# VCF-LM324-Stereo-Perfboard.net
KiCad netlist of a schematic drawn in EAGLE
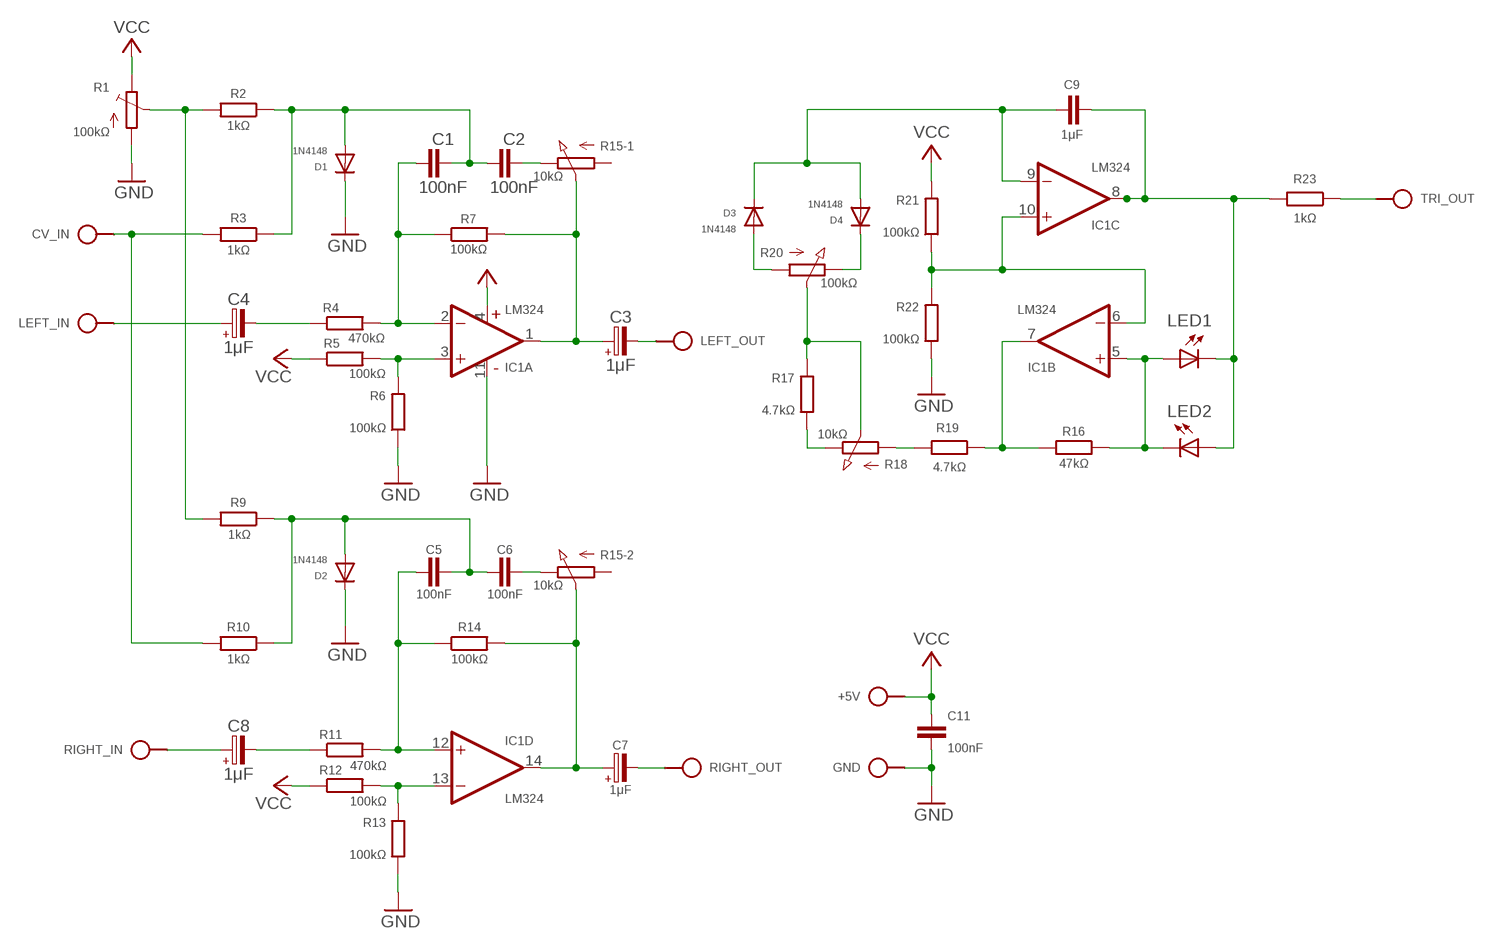
[diagram p0: schematic, sheet 1]

(export (version "E")
  (design (tool "Eeschema 10.0.6"))
  (components
    (comp (ref "+5V")
      (value "VCC")
      (footprint "eagle-import:SPAD")
      (libsource (lib "eagle-import") (part "SPAD"))
    )
    (comp (ref "C1")
      (value "100nF")
      (footprint "eagle-import:C050-024X044")
      (libsource (lib "eagle-import") (part "C050-024X044"))
    )
    (comp (ref "C2")
      (value "100nF")
      (footprint "eagle-import:C050-024X044")
      (libsource (lib "eagle-import") (part "C050-024X044"))
    )
    (comp (ref "C3")
      (value "1μF")
      (footprint "eagle-import:E2,5-3")
      (libsource (lib "eagle-import") (part "CPOLE2,5-3"))
    )
    (comp (ref "C4")
      (value "1μF")
      (footprint "eagle-import:E2,5-3")
      (libsource (lib "eagle-import") (part "CPOLE2,5-3"))
    )
    (comp (ref "C5")
      (value "100nF")
      (footprint "eagle-import:C050-024X044")
      (libsource (lib "eagle-import") (part "C050-024X044"))
    )
    (comp (ref "C6")
      (value "100nF")
      (footprint "eagle-import:C050-024X044")
      (libsource (lib "eagle-import") (part "C050-024X044"))
    )
    (comp (ref "C7")
      (value "1μF")
      (footprint "eagle-import:E2,5-3")
      (libsource (lib "eagle-import") (part "CPOLE2,5-3"))
    )
    (comp (ref "C8")
      (value "1μF")
      (footprint "eagle-import:E2,5-3")
      (libsource (lib "eagle-import") (part "CPOLE2,5-3"))
    )
    (comp (ref "C9")
      (value "1μF")
      (footprint "eagle-import:C050-024X044")
      (libsource (lib "eagle-import") (part "C050-024X044"))
    )
    (comp (ref "C11")
      (value "100nF")
      (footprint "eagle-import:C050-020X036")
      (libsource (lib "eagle-import") (part "C050-020X036"))
    )
    (comp (ref "CV_IN")
      (value "CV_IN")
      (footprint "eagle-import:SPAD")
      (libsource (lib "eagle-import") (part "SPAD"))
    )
    (comp (ref "D1")
      (value "1N4148")
      (footprint "eagle-import:DO34-10V")
      (libsource (lib "eagle-import") (part "1N414834-10V"))
    )
    (comp (ref "D2")
      (value "1N4148")
      (footprint "eagle-import:DO34-7V")
      (libsource (lib "eagle-import") (part "1N414834-7V"))
    )
    (comp (ref "D3")
      (value "1N4148")
      (footprint "eagle-import:DO34-7V")
      (libsource (lib "eagle-import") (part "1N414834-7V"))
    )
    (comp (ref "D4")
      (value "1N4148")
      (footprint "eagle-import:DO34-7V")
      (libsource (lib "eagle-import") (part "1N414834-7V"))
    )
    (comp (ref "GND")
      (value "GND")
      (footprint "eagle-import:SPAD")
      (libsource (lib "eagle-import") (part "SPAD"))
    )
    (comp (ref "IC1")
      (value "LM324")
      (footprint "eagle-import:DIL14")
      (libsource (lib "eagle-import") (part "LM324N"))
    )
    (comp (ref "LED1")
      (value "LED3MM")
      (footprint "eagle-import:LED3MM")
      (libsource (lib "eagle-import") (part "LED3MM"))
    )
    (comp (ref "LED2")
      (value "LED3MM")
      (footprint "eagle-import:LED3MM")
      (libsource (lib "eagle-import") (part "LED3MM"))
    )
    (comp (ref "LEFT_IN")
      (value "AUDIO_IN")
      (footprint "eagle-import:SPAD")
      (libsource (lib "eagle-import") (part "SPAD"))
    )
    (comp (ref "LEFT_OUT")
      (value "AUDIO_OUT")
      (footprint "eagle-import:SPAD")
      (libsource (lib "eagle-import") (part "SPAD"))
    )
    (comp (ref "R1")
      (value "100kΩ")
      (footprint "eagle-import:B64Y")
      (libsource (lib "eagle-import") (part "TRIM"))
    )
    (comp (ref "R2")
      (value "1kΩ")
      (footprint "eagle-import:0202_7")
      (libsource (lib "eagle-import") (part "R0202/7"))
    )
    (comp (ref "R3")
      (value "1kΩ")
      (footprint "eagle-import:0202_7")
      (libsource (lib "eagle-import") (part "R0202/7"))
    )
    (comp (ref "R4")
      (value "470kΩ")
      (footprint "eagle-import:0202_7")
      (libsource (lib "eagle-import") (part "R0202/7"))
    )
    (comp (ref "R5")
      (value "100kΩ")
      (footprint "eagle-import:0204_7")
      (libsource (lib "eagle-import") (part "R0204/7"))
    )
    (comp (ref "R6")
      (value "100kΩ")
      (footprint "eagle-import:0202_7")
      (libsource (lib "eagle-import") (part "R0202/7"))
    )
    (comp (ref "R7")
      (value "100kΩ")
      (footprint "eagle-import:0204_7")
      (libsource (lib "eagle-import") (part "R0204/7"))
    )
    (comp (ref "R9")
      (value "1kΩ")
      (footprint "eagle-import:0202_10")
      (libsource (lib "eagle-import") (part "R0202/10"))
    )
    (comp (ref "R10")
      (value "1kΩ")
      (footprint "eagle-import:0202_10")
      (libsource (lib "eagle-import") (part "R0202/10"))
    )
    (comp (ref "R11")
      (value "470kΩ")
      (footprint "eagle-import:0202_7")
      (libsource (lib "eagle-import") (part "R0202/7"))
    )
    (comp (ref "R12")
      (value "100kΩ")
      (footprint "eagle-import:0202_7")
      (libsource (lib "eagle-import") (part "R0202/7"))
    )
    (comp (ref "R13")
      (value "100kΩ")
      (footprint "eagle-import:0202_7")
      (libsource (lib "eagle-import") (part "R0202/7"))
    )
    (comp (ref "R14")
      (value "100kΩ")
      (footprint "eagle-import:0204_10")
      (libsource (lib "eagle-import") (part "R0204/10"))
    )
    (comp (ref "R15")
      (value "10kΩ")
      (footprint "eagle-import:POT-STEREO-2X3")
      (libsource (lib "eagle-import") (part "POT-STEREO"))
    )
    (comp (ref "R16")
      (value "47kΩ")
      (footprint "eagle-import:0202_7-V")
      (libsource (lib "eagle-import") (part "R0202/7-V"))
    )
    (comp (ref "R17")
      (value "4.7kΩ")
      (footprint "eagle-import:0202_7")
      (libsource (lib "eagle-import") (part "R0202/7"))
    )
    (comp (ref "R18")
      (value "10kΩ")
      (footprint "eagle-import:POT")
      (libsource (lib "eagle-import") (part "POT"))
    )
    (comp (ref "R19")
      (value "4.7kΩ")
      (footprint "eagle-import:0202_7-V")
      (libsource (lib "eagle-import") (part "R0202/7-V"))
    )
    (comp (ref "R20")
      (value "100kΩ")
      (footprint "eagle-import:POT")
      (libsource (lib "eagle-import") (part "POT"))
    )
    (comp (ref "R21")
      (value "100kΩ")
      (footprint "eagle-import:0202_7-V")
      (libsource (lib "eagle-import") (part "R0202/7-V"))
    )
    (comp (ref "R22")
      (value "100kΩ")
      (footprint "eagle-import:0202_7-V")
      (libsource (lib "eagle-import") (part "R0202/7-V"))
    )
    (comp (ref "R23")
      (value "1kΩ")
      (footprint "eagle-import:0202_7-V")
      (libsource (lib "eagle-import") (part "R0202/7-V"))
    )
    (comp (ref "RIGHT_IN")
      (value "AUDIO_IN")
      (footprint "eagle-import:SPAD")
      (libsource (lib "eagle-import") (part "SPAD"))
    )
    (comp (ref "RIGHT_OUT")
      (value "AUDIO_OUT")
      (footprint "eagle-import:SPAD")
      (libsource (lib "eagle-import") (part "SPAD"))
    )
    (comp (ref "TRI_OUT")
      (value "TRIANGLE")
      (footprint "eagle-import:SPAD")
      (libsource (lib "eagle-import") (part "SPAD"))
    )
  )
  (nets
    (net (code "1") (name "GND") (class "Default")
      (node (ref "C11") (pin "2") (pinfunction "2_2") (pintype "passive"))
      (node (ref "D1") (pin "C") (pinfunction "C_C") (pintype "passive"))
      (node (ref "D2") (pin "C") (pinfunction "C_C") (pintype "passive"))
      (node (ref "GND") (pin "1") (pinfunction "P$1_1") (pintype "bidirectional"))
      (node (ref "IC1") (pin "11") (pinfunction "V-_11") (pintype "power_in"))
      (node (ref "R1") (pin "A") (pinfunction "A_A") (pintype "passive"))
      (node (ref "R13") (pin "1") (pinfunction "1_1") (pintype "passive"))
      (node (ref "R22") (pin "1") (pinfunction "1_1") (pintype "passive"))
      (node (ref "R6") (pin "1") (pinfunction "1_1") (pintype "passive"))
    )
    (net (code "2") (name "Net-(C1-Pad2)") (class "Default")
      (node (ref "C1") (pin "2") (pinfunction "2_2") (pintype "passive"))
      (node (ref "C2") (pin "1") (pinfunction "1_1") (pintype "passive"))
      (node (ref "D1") (pin "A") (pinfunction "A_A") (pintype "passive"))
      (node (ref "R2") (pin "1") (pinfunction "1_1") (pintype "passive"))
      (node (ref "R3") (pin "1") (pinfunction "1_1") (pintype "passive"))
    )
    (net (code "3") (name "Net-(C4-Pad-)") (class "Default")
      (node (ref "C4") (pin "-") (pinfunction "-_-") (pintype "passive"))
      (node (ref "R4") (pin "1") (pinfunction "1_1") (pintype "passive"))
    )
    (net (code "4") (name "Net-(C5-Pad2)") (class "Default")
      (node (ref "C5") (pin "2") (pinfunction "2_2") (pintype "passive"))
      (node (ref "C6") (pin "1") (pinfunction "1_1") (pintype "passive"))
      (node (ref "D2") (pin "A") (pinfunction "A_A") (pintype "passive"))
      (node (ref "R10") (pin "1") (pinfunction "1_1") (pintype "passive"))
      (node (ref "R9") (pin "1") (pinfunction "1_1") (pintype "passive"))
    )
    (net (code "5") (name "Net-(C8-Pad-)") (class "Default")
      (node (ref "C8") (pin "-") (pinfunction "-_-") (pintype "passive"))
      (node (ref "R11") (pin "1") (pinfunction "1_1") (pintype "passive"))
    )
    (net (code "6") (name "Net-(CV_IN-P$1)") (class "Default")
      (node (ref "CV_IN") (pin "1") (pinfunction "P$1_1") (pintype "bidirectional"))
      (node (ref "R10") (pin "2") (pinfunction "2_2") (pintype "passive"))
      (node (ref "R3") (pin "2") (pinfunction "2_2") (pintype "passive"))
    )
    (net (code "7") (name "Net-(IC1A-+IN)") (class "Default")
      (node (ref "IC1") (pin "3") (pinfunction "+IN_3") (pintype "input"))
      (node (ref "R5") (pin "2") (pinfunction "2_2") (pintype "passive"))
      (node (ref "R6") (pin "2") (pinfunction "2_2") (pintype "passive"))
    )
    (net (code "8") (name "Net-(IC1A--IN)") (class "Default")
      (node (ref "C1") (pin "1") (pinfunction "1_1") (pintype "passive"))
      (node (ref "IC1") (pin "2") (pinfunction "-IN_2") (pintype "input"))
      (node (ref "R4") (pin "2") (pinfunction "2_2") (pintype "passive"))
      (node (ref "R7") (pin "1") (pinfunction "1_1") (pintype "passive"))
    )
    (net (code "9") (name "Net-(IC1A-OUT)") (class "Default")
      (node (ref "C3") (pin "+") (pinfunction "+_+") (pintype "passive"))
      (node (ref "IC1") (pin "1") (pinfunction "OUT_1") (pintype "output"))
      (node (ref "R15") (pin "1-S") (pinfunction "S_1-S") (pintype "passive"))
      (node (ref "R7") (pin "2") (pinfunction "2_2") (pintype "passive"))
    )
    (net (code "10") (name "Net-(IC1B-+IN)") (class "Default")
      (node (ref "IC1") (pin "5") (pinfunction "+IN_5") (pintype "input"))
      (node (ref "LED1") (pin "A") (pinfunction "A_A") (pintype "passive"))
      (node (ref "LED2") (pin "K") (pinfunction "C_K") (pintype "passive"))
      (node (ref "R16") (pin "1") (pinfunction "1_1") (pintype "passive"))
    )
    (net (code "11") (name "Net-(IC1B--IN)") (class "Default")
      (node (ref "IC1") (pin "10") (pinfunction "+IN_10") (pintype "input"))
      (node (ref "IC1") (pin "6") (pinfunction "-IN_6") (pintype "input"))
      (node (ref "R21") (pin "1") (pinfunction "1_1") (pintype "passive"))
      (node (ref "R22") (pin "2") (pinfunction "2_2") (pintype "passive"))
    )
    (net (code "12") (name "Net-(IC1B-OUT)") (class "Default")
      (node (ref "IC1") (pin "7") (pinfunction "OUT_7") (pintype "output"))
      (node (ref "R16") (pin "2") (pinfunction "2_2") (pintype "passive"))
      (node (ref "R19") (pin "1") (pinfunction "1_1") (pintype "passive"))
    )
    (net (code "13") (name "Net-(IC1C--IN)") (class "Default")
      (node (ref "C9") (pin "1") (pinfunction "1_1") (pintype "passive"))
      (node (ref "D3") (pin "C") (pinfunction "C_C") (pintype "passive"))
      (node (ref "D4") (pin "A") (pinfunction "A_A") (pintype "passive"))
      (node (ref "IC1") (pin "9") (pinfunction "-IN_9") (pintype "input"))
    )
    (net (code "14") (name "Net-(IC1C-OUT)") (class "Default")
      (node (ref "C9") (pin "2") (pinfunction "2_2") (pintype "passive"))
      (node (ref "IC1") (pin "8") (pinfunction "OUT_8") (pintype "output"))
      (node (ref "LED1") (pin "K") (pinfunction "C_K") (pintype "passive"))
      (node (ref "LED2") (pin "A") (pinfunction "A_A") (pintype "passive"))
      (node (ref "R23") (pin "2") (pinfunction "2_2") (pintype "passive"))
    )
    (net (code "15") (name "Net-(IC1D-+IN)") (class "Default")
      (node (ref "C5") (pin "1") (pinfunction "1_1") (pintype "passive"))
      (node (ref "IC1") (pin "12") (pinfunction "+IN_12") (pintype "input"))
      (node (ref "R11") (pin "2") (pinfunction "2_2") (pintype "passive"))
      (node (ref "R14") (pin "1") (pinfunction "1_1") (pintype "passive"))
    )
    (net (code "16") (name "Net-(IC1D--IN)") (class "Default")
      (node (ref "IC1") (pin "13") (pinfunction "-IN_13") (pintype "input"))
      (node (ref "R12") (pin "2") (pinfunction "2_2") (pintype "passive"))
      (node (ref "R13") (pin "2") (pinfunction "2_2") (pintype "passive"))
    )
    (net (code "17") (name "Net-(IC1D-OUT)") (class "Default")
      (node (ref "C7") (pin "+") (pinfunction "+_+") (pintype "passive"))
      (node (ref "IC1") (pin "14") (pinfunction "OUT_14") (pintype "output"))
      (node (ref "R14") (pin "2") (pinfunction "2_2") (pintype "passive"))
      (node (ref "R15") (pin "2-S") (pinfunction "S_2-S") (pintype "passive"))
    )
    (net (code "18") (name "Net-(LEFT_IN-P$1)") (class "Default")
      (node (ref "C4") (pin "+") (pinfunction "+_+") (pintype "passive"))
      (node (ref "LEFT_IN") (pin "1") (pinfunction "P$1_1") (pintype "bidirectional"))
    )
    (net (code "19") (name "Net-(LEFT_OUT-P$1)") (class "Default")
      (node (ref "C3") (pin "-") (pinfunction "-_-") (pintype "passive"))
      (node (ref "LEFT_OUT") (pin "1") (pinfunction "P$1_1") (pintype "bidirectional"))
    )
    (net (code "20") (name "Net-(R1-PadS)") (class "Default")
      (node (ref "R1") (pin "S") (pinfunction "S_S") (pintype "passive"))
      (node (ref "R2") (pin "2") (pinfunction "2_2") (pintype "passive"))
      (node (ref "R9") (pin "2") (pinfunction "2_2") (pintype "passive"))
    )
    (net (code "21") (name "Net-(R15A-E)") (class "Default")
      (node (ref "C2") (pin "2") (pinfunction "2_2") (pintype "passive"))
      (node (ref "R15") (pin "1-E") (pinfunction "E_1-E") (pintype "passive"))
    )
    (net (code "22") (name "Net-(R15B-E)") (class "Default")
      (node (ref "C6") (pin "2") (pinfunction "2_2") (pintype "passive"))
      (node (ref "R15") (pin "2-E") (pinfunction "E_2-E") (pintype "passive"))
    )
    (net (code "23") (name "Net-(R18-A)") (class "Default")
      (node (ref "R18") (pin "1") (pinfunction "A_1") (pintype "passive"))
      (node (ref "R19") (pin "2") (pinfunction "2_2") (pintype "passive"))
    )
    (net (code "24") (name "Net-(R18-E)") (class "Default")
      (node (ref "R17") (pin "1") (pinfunction "1_1") (pintype "passive"))
      (node (ref "R18") (pin "3") (pinfunction "E_3") (pintype "passive"))
    )
    (net (code "25") (name "Net-(R18-S)") (class "Default")
      (node (ref "R17") (pin "2") (pinfunction "2_2") (pintype "passive"))
      (node (ref "R18") (pin "2") (pinfunction "S_2") (pintype "passive"))
      (node (ref "R20") (pin "2") (pinfunction "S_2") (pintype "passive"))
    )
    (net (code "26") (name "Net-(R20-A)") (class "Default")
      (node (ref "D3") (pin "A") (pinfunction "A_A") (pintype "passive"))
      (node (ref "R20") (pin "1") (pinfunction "A_1") (pintype "passive"))
    )
    (net (code "27") (name "Net-(R20-E)") (class "Default")
      (node (ref "D4") (pin "C") (pinfunction "C_C") (pintype "passive"))
      (node (ref "R20") (pin "3") (pinfunction "E_3") (pintype "passive"))
    )
    (net (code "28") (name "Net-(RIGHT_IN-P$1)") (class "Default")
      (node (ref "C8") (pin "+") (pinfunction "+_+") (pintype "passive"))
      (node (ref "RIGHT_IN") (pin "1") (pinfunction "P$1_1") (pintype "bidirectional"))
    )
    (net (code "29") (name "Net-(RIGHT_OUT-P$1)") (class "Default")
      (node (ref "C7") (pin "-") (pinfunction "-_-") (pintype "passive"))
      (node (ref "RIGHT_OUT") (pin "1") (pinfunction "P$1_1") (pintype "bidirectional"))
    )
    (net (code "30") (name "Net-(TRI_OUT-P$1)") (class "Default")
      (node (ref "R23") (pin "1") (pinfunction "1_1") (pintype "passive"))
      (node (ref "TRI_OUT") (pin "1") (pinfunction "P$1_1") (pintype "bidirectional"))
    )
    (net (code "31") (name "VCC") (class "Default")
      (node (ref "+5V") (pin "1") (pinfunction "P$1_1") (pintype "bidirectional"))
      (node (ref "C11") (pin "1") (pinfunction "1_1") (pintype "passive"))
      (node (ref "IC1") (pin "4") (pinfunction "V+_4") (pintype "power_in"))
      (node (ref "R1") (pin "E") (pinfunction "E_E") (pintype "passive"))
      (node (ref "R12") (pin "1") (pinfunction "1_1") (pintype "passive"))
      (node (ref "R21") (pin "2") (pinfunction "2_2") (pintype "passive"))
      (node (ref "R5") (pin "1") (pinfunction "1_1") (pintype "passive"))
    )
    (net (code "32") (name "unconnected-(R15A-A-Pad1-A)") (class "Default")
      (node (ref "R15") (pin "1-A") (pinfunction "A_1-A") (pintype "passive"))
    )
    (net (code "33") (name "unconnected-(R15B-A-Pad2-A)") (class "Default")
      (node (ref "R15") (pin "2-A") (pinfunction "A_2-A") (pintype "passive"))
    )
  )
)
